# Modemplatine_modem_1_1.net
KiCad netlist of a schematic drawn in EAGLE
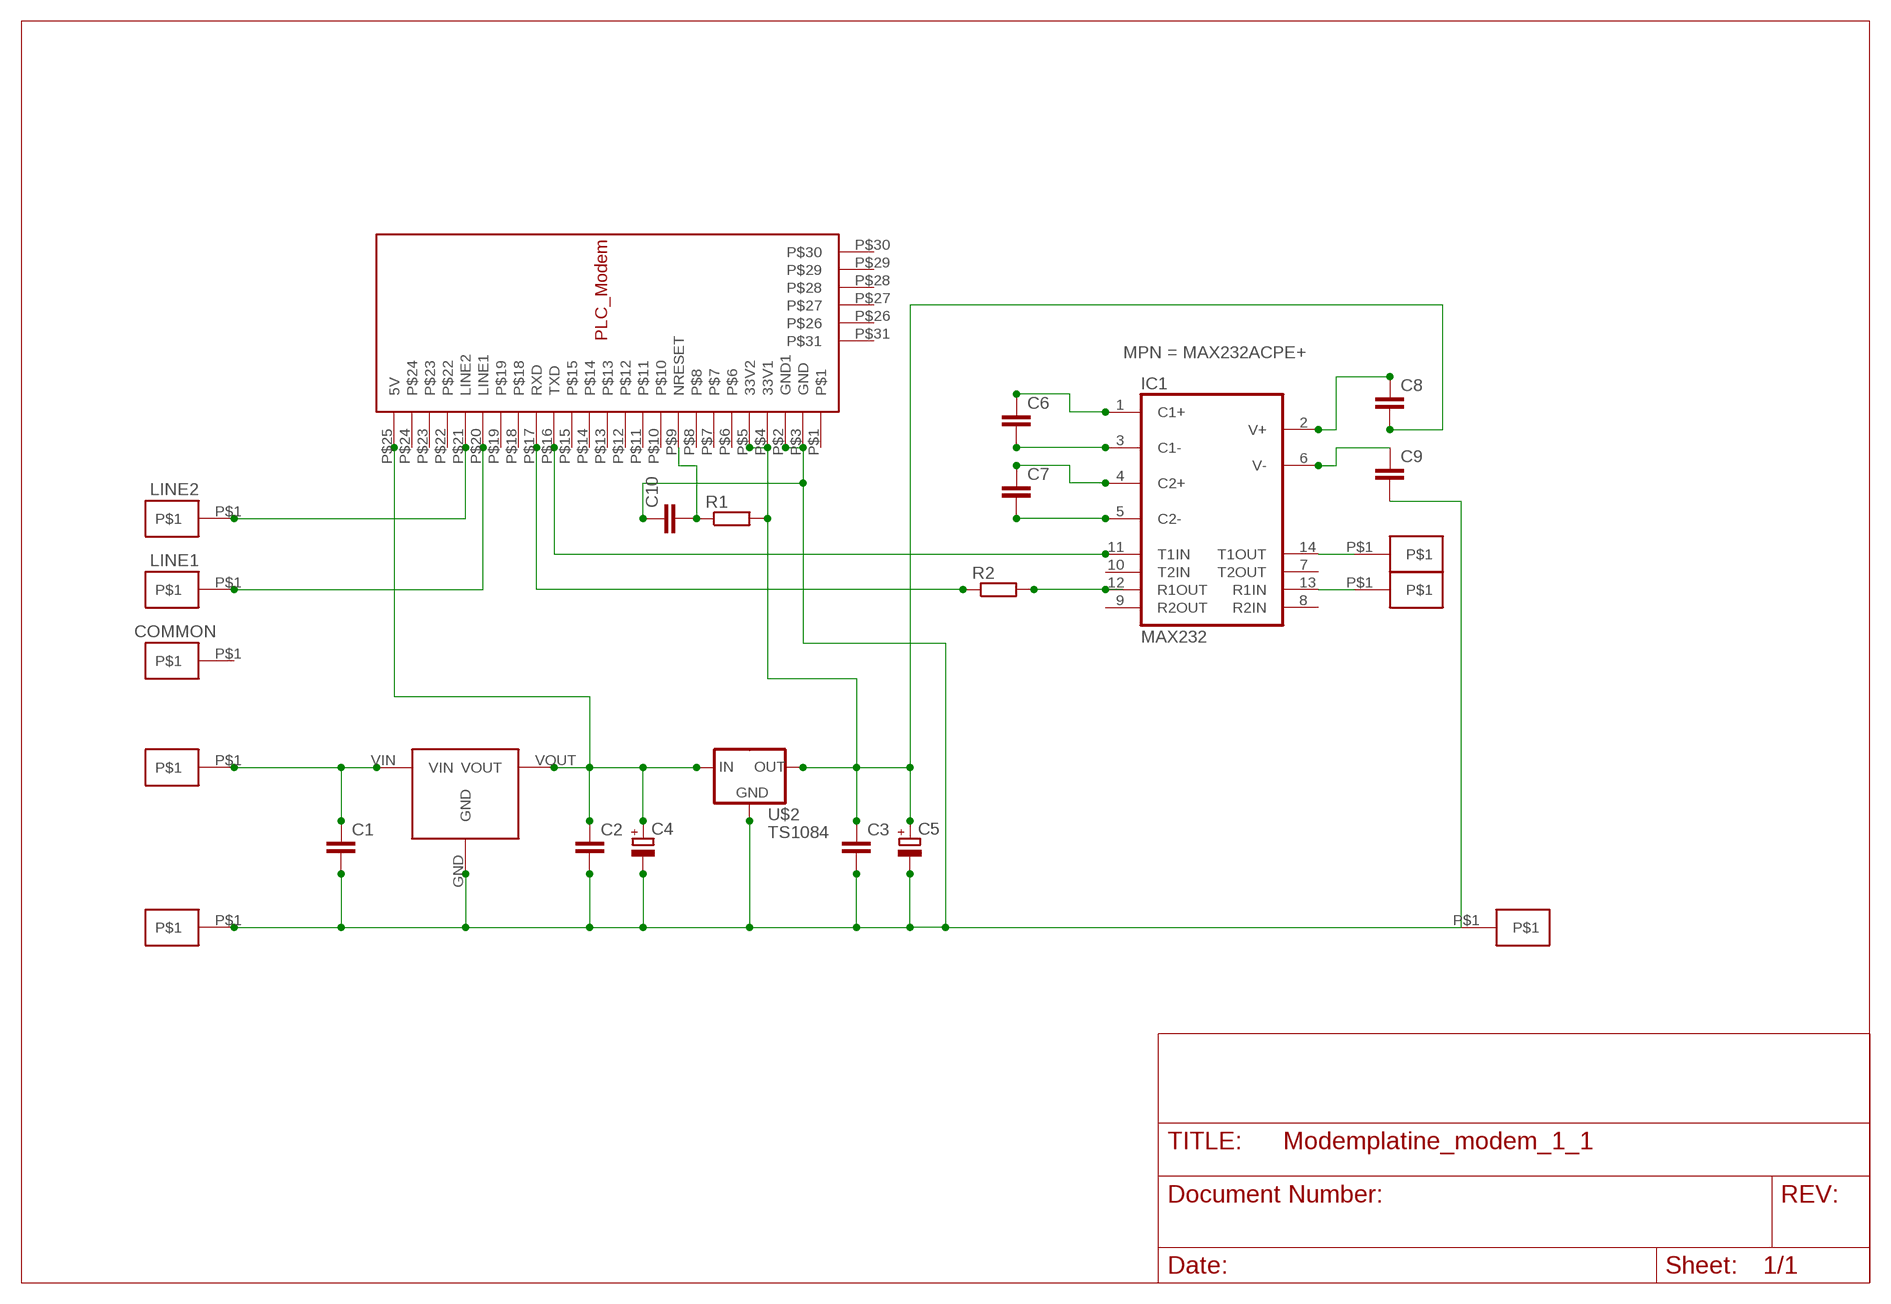
[diagram p0: schematic, sheet 1]

(export (version "E")
  (design (tool "Eeschema 10.0.6"))
  (components
    (comp (ref "C1")
      (value "C2.5/5")
      (footprint "eagle-import:C2.5-5")
      (libsource (lib "eagle-import") (part "C2.5/5"))
    )
    (comp (ref "C2")
      (value "C2.5/5")
      (footprint "eagle-import:C2.5-5")
      (libsource (lib "eagle-import") (part "C2.5/5"))
    )
    (comp (ref "C3")
      (value "C2.5/5")
      (footprint "eagle-import:C2.5-5")
      (libsource (lib "eagle-import") (part "C2.5/5"))
    )
    (comp (ref "C4")
      (value "CPOL-EUE2.5-5")
      (footprint "eagle-import:E2,5-5")
      (libsource (lib "eagle-import") (part "CPOL-EUE2.5-5"))
    )
    (comp (ref "C5")
      (value "CPOL-EUE2.5-5")
      (footprint "eagle-import:E2,5-5")
      (libsource (lib "eagle-import") (part "CPOL-EUE2.5-5"))
    )
    (comp (ref "C6")
      (value "C-EU025-040X050")
      (footprint "eagle-import:C025-040X050")
      (libsource (lib "eagle-import") (part "C-EU025-040X050"))
    )
    (comp (ref "C7")
      (value "C-EU025-040X050")
      (footprint "eagle-import:C025-040X050")
      (libsource (lib "eagle-import") (part "C-EU025-040X050"))
    )
    (comp (ref "C8")
      (value "C-EU025-040X050")
      (footprint "eagle-import:C025-040X050")
      (libsource (lib "eagle-import") (part "C-EU025-040X050"))
    )
    (comp (ref "C9")
      (value "C-EU025-040X050")
      (footprint "eagle-import:C025-040X050")
      (libsource (lib "eagle-import") (part "C-EU025-040X050"))
    )
    (comp (ref "C10")
      (value "C-EU025-040X050")
      (footprint "eagle-import:C025-040X050")
      (libsource (lib "eagle-import") (part "C-EU025-040X050"))
    )
    (comp (ref "IC1")
      (value "MAX232")
      (footprint "eagle-import:DIL16")
      (fields
        (field (name "MF") "MAXIM")
        (field (name "MPN") "MAX232ACPE+")
        (field (name "MPN_1") "MAX232ACPE+")
      )
      (libsource (lib "eagle-import") (part "MAX232"))
    )
    (comp (ref "LINE1")
      (value "PN4")
      (footprint "eagle-import:PIN2")
      (libsource (lib "eagle-import") (part "PN4"))
    )
    (comp (ref "LINE2")
      (value "PN4")
      (footprint "eagle-import:PIN2")
      (libsource (lib "eagle-import") (part "PN4"))
    )
    (comp (ref "R1")
      (value "R-EU_0207/10")
      (footprint "eagle-import:0207_10")
      (libsource (lib "eagle-import") (part "R-EU_0207/10"))
    )
    (comp (ref "R2")
      (value "R-EU_0207/10")
      (footprint "eagle-import:0207_10")
      (libsource (lib "eagle-import") (part "R-EU_0207/10"))
    )
    (comp (ref "U$1")
      (value "RECOM_785_05")
      (footprint "eagle-import:RECOM785X")
      (libsource (lib "eagle-import") (part "RECOM_785_05"))
    )
    (comp (ref "U$2")
      (value "TS1084")
      (footprint "eagle-import:TS1084")
      (libsource (lib "eagle-import") (part "TS1084"))
    )
    (comp (ref "U$3")
      (value "MODEMSTECKER")
      (footprint "eagle-import:MODEM_FUSS")
      (libsource (lib "eagle-import") (part "MODEMSTECKER"))
    )
    (comp (ref "U$4")
      (value "PN4")
      (footprint "eagle-import:PIN2")
      (libsource (lib "eagle-import") (part "PN4"))
    )
    (comp (ref "U$5")
      (value "PN4")
      (footprint "eagle-import:PIN2")
      (libsource (lib "eagle-import") (part "PN4"))
    )
    (comp (ref "U$6")
      (value "PN4")
      (footprint "eagle-import:PIN2")
      (libsource (lib "eagle-import") (part "PN4"))
    )
    (comp (ref "U$7")
      (value "PN4")
      (footprint "eagle-import:PIN2")
      (libsource (lib "eagle-import") (part "PN4"))
    )
    (comp (ref "U$8")
      (value "PN4")
      (footprint "eagle-import:PIN2")
      (libsource (lib "eagle-import") (part "PN4"))
    )
    (comp (ref "U$11")
      (value "PN4")
      (footprint "eagle-import:PIN2")
      (libsource (lib "eagle-import") (part "PN4"))
    )
  )
  (nets
    (net (code "1") (name "Net-(C1-Pad1)") (class "Default")
      (node (ref "C1") (pin "1") (pinfunction "1_1") (pintype "passive"))
      (node (ref "U$1") (pin "VIN") (pinfunction "VIN_VIN") (pintype "bidirectional"))
      (node (ref "U$5") (pin "P$1") (pinfunction "P$1_P$1") (pintype "bidirectional"))
    )
    (net (code "2") (name "Net-(IC1A-C1+)") (class "Default")
      (node (ref "C6") (pin "1") (pinfunction "1_1") (pintype "passive"))
      (node (ref "IC1") (pin "1") (pinfunction "C1+_1") (pintype "bidirectional"))
    )
    (net (code "3") (name "Net-(IC1A-C1-)") (class "Default")
      (node (ref "C6") (pin "2") (pinfunction "2_2") (pintype "passive"))
      (node (ref "IC1") (pin "3") (pinfunction "C1-_3") (pintype "bidirectional"))
    )
    (net (code "4") (name "Net-(IC1A-C2+)") (class "Default")
      (node (ref "C7") (pin "1") (pinfunction "1_1") (pintype "passive"))
      (node (ref "IC1") (pin "4") (pinfunction "C2+_4") (pintype "bidirectional"))
    )
    (net (code "5") (name "Net-(IC1A-C2-)") (class "Default")
      (node (ref "C7") (pin "2") (pinfunction "2_2") (pintype "passive"))
      (node (ref "IC1") (pin "5") (pinfunction "C2-_5") (pintype "bidirectional"))
    )
    (net (code "6") (name "Net-(IC1A-R1IN)") (class "Default")
      (node (ref "IC1") (pin "13") (pinfunction "R1IN_13") (pintype "input"))
      (node (ref "U$7") (pin "P$1") (pinfunction "P$1_P$1") (pintype "bidirectional"))
    )
    (net (code "7") (name "Net-(IC1A-R1OUT)") (class "Default")
      (node (ref "IC1") (pin "12") (pinfunction "R1OUT_12") (pintype "output"))
      (node (ref "R2") (pin "2") (pinfunction "2_2") (pintype "passive"))
    )
    (net (code "8") (name "Net-(IC1A-T1IN)") (class "Default")
      (node (ref "IC1") (pin "11") (pinfunction "T1IN_11") (pintype "input"))
      (node (ref "U$3") (pin "P$16") (pinfunction "TXD_P$16") (pintype "bidirectional"))
    )
    (net (code "9") (name "Net-(IC1A-T1OUT)") (class "Default")
      (node (ref "IC1") (pin "14") (pinfunction "T1OUT_14") (pintype "output"))
      (node (ref "U$6") (pin "P$1") (pinfunction "P$1_P$1") (pintype "bidirectional"))
    )
    (net (code "10") (name "Net-(IC1A-V+)") (class "Default")
      (node (ref "C8") (pin "1") (pinfunction "1_1") (pintype "passive"))
      (node (ref "IC1") (pin "2") (pinfunction "V+_2") (pintype "bidirectional"))
    )
    (net (code "11") (name "Net-(IC1A-V-)") (class "Default")
      (node (ref "C9") (pin "1") (pinfunction "1_1") (pintype "passive"))
      (node (ref "IC1") (pin "6") (pinfunction "V-_6") (pintype "bidirectional"))
    )
    (net (code "12") (name "Net-(U$2-GND)") (class "Default")
      (node (ref "C1") (pin "2") (pinfunction "2_2") (pintype "passive"))
      (node (ref "C10") (pin "1") (pinfunction "1_1") (pintype "passive"))
      (node (ref "C2") (pin "2") (pinfunction "2_2") (pintype "passive"))
      (node (ref "C3") (pin "2") (pinfunction "2_2") (pintype "passive"))
      (node (ref "C4") (pin "-") (pinfunction "-_-") (pintype "passive"))
      (node (ref "C5") (pin "-") (pinfunction "-_-") (pintype "passive"))
      (node (ref "C9") (pin "2") (pinfunction "2_2") (pintype "passive"))
      (node (ref "U$1") (pin "GND") (pinfunction "GND_GND") (pintype "bidirectional"))
      (node (ref "U$2") (pin "1GND") (pinfunction "GND_1GND") (pintype "input"))
      (node (ref "U$3") (pin "P$2") (pinfunction "GND1_P$2") (pintype "bidirectional"))
      (node (ref "U$3") (pin "P$3") (pinfunction "GND_P$3") (pintype "bidirectional"))
      (node (ref "U$4") (pin "P$1") (pinfunction "P$1_P$1") (pintype "bidirectional"))
      (node (ref "U$8") (pin "P$1") (pinfunction "P$1_P$1") (pintype "bidirectional"))
    )
    (net (code "13") (name "Net-(U$2-IN)") (class "Default")
      (node (ref "C2") (pin "1") (pinfunction "1_1") (pintype "passive"))
      (node (ref "C4") (pin "+") (pinfunction "+_+") (pintype "passive"))
      (node (ref "U$1") (pin "VOUT") (pinfunction "VOUT_VOUT") (pintype "bidirectional"))
      (node (ref "U$2") (pin "3IN") (pinfunction "IN_3IN") (pintype "input"))
      (node (ref "U$3") (pin "P$25") (pinfunction "5V_P$25") (pintype "bidirectional"))
    )
    (net (code "14") (name "Net-(U$2-OUT)") (class "Default")
      (node (ref "C3") (pin "1") (pinfunction "1_1") (pintype "passive"))
      (node (ref "C5") (pin "+") (pinfunction "+_+") (pintype "passive"))
      (node (ref "C8") (pin "2") (pinfunction "2_2") (pintype "passive"))
      (node (ref "R1") (pin "2") (pinfunction "2_2") (pintype "passive"))
      (node (ref "U$2") (pin "2OUT") (pinfunction "OUT_2OUT") (pintype "passive"))
      (node (ref "U$3") (pin "P$4") (pinfunction "33V1_P$4") (pintype "bidirectional"))
      (node (ref "U$3") (pin "P$5") (pinfunction "33V2_P$5") (pintype "bidirectional"))
    )
    (net (code "15") (name "Net-(U$3-LINE1)") (class "Default")
      (node (ref "LINE1") (pin "P$1") (pinfunction "P$1_P$1") (pintype "bidirectional"))
      (node (ref "U$3") (pin "P$20") (pinfunction "LINE1_P$20") (pintype "bidirectional"))
    )
    (net (code "16") (name "Net-(U$3-LINE2)") (class "Default")
      (node (ref "LINE2") (pin "P$1") (pinfunction "P$1_P$1") (pintype "bidirectional"))
      (node (ref "U$3") (pin "P$21") (pinfunction "LINE2_P$21") (pintype "bidirectional"))
    )
    (net (code "17") (name "Net-(U$3-NRESET)") (class "Default")
      (node (ref "C10") (pin "2") (pinfunction "2_2") (pintype "passive"))
      (node (ref "R1") (pin "1") (pinfunction "1_1") (pintype "passive"))
      (node (ref "U$3") (pin "P$9") (pinfunction "NRESET_P$9") (pintype "bidirectional"))
    )
    (net (code "18") (name "Net-(U$3-RXD)") (class "Default")
      (node (ref "R2") (pin "1") (pinfunction "1_1") (pintype "passive"))
      (node (ref "U$3") (pin "P$17") (pinfunction "RXD_P$17") (pintype "bidirectional"))
    )
    (net (code "19") (name "unconnected-(IC1A-R2IN-Pad8)") (class "Default")
      (node (ref "IC1") (pin "8") (pinfunction "R2IN_8") (pintype "input"))
    )
    (net (code "20") (name "unconnected-(IC1A-R2OUT-Pad9)") (class "Default")
      (node (ref "IC1") (pin "9") (pinfunction "R2OUT_9") (pintype "output"))
    )
    (net (code "21") (name "unconnected-(IC1A-T2IN-Pad10)") (class "Default")
      (node (ref "IC1") (pin "10") (pinfunction "T2IN_10") (pintype "input"))
    )
    (net (code "22") (name "unconnected-(IC1A-T2OUT-Pad7)") (class "Default")
      (node (ref "IC1") (pin "7") (pinfunction "T2OUT_7") (pintype "output"))
    )
    (net (code "23") (name "unconnected-(U$3-PadP$1)") (class "Default")
      (node (ref "U$3") (pin "P$1") (pinfunction "P$1_P$1") (pintype "bidirectional"))
    )
    (net (code "24") (name "unconnected-(U$3-PadP$6)") (class "Default")
      (node (ref "U$3") (pin "P$6") (pinfunction "P$6_P$6") (pintype "bidirectional"))
    )
    (net (code "25") (name "unconnected-(U$3-PadP$7)") (class "Default")
      (node (ref "U$3") (pin "P$7") (pinfunction "P$7_P$7") (pintype "bidirectional"))
    )
    (net (code "26") (name "unconnected-(U$3-PadP$8)") (class "Default")
      (node (ref "U$3") (pin "P$8") (pinfunction "P$8_P$8") (pintype "bidirectional"))
    )
    (net (code "27") (name "unconnected-(U$3-PadP$10)") (class "Default")
      (node (ref "U$3") (pin "P$10") (pinfunction "P$10_P$10") (pintype "bidirectional"))
    )
    (net (code "28") (name "unconnected-(U$3-PadP$11)") (class "Default")
      (node (ref "U$3") (pin "P$11") (pinfunction "P$11_P$11") (pintype "bidirectional"))
    )
    (net (code "29") (name "unconnected-(U$3-PadP$12)") (class "Default")
      (node (ref "U$3") (pin "P$12") (pinfunction "P$12_P$12") (pintype "bidirectional"))
    )
    (net (code "30") (name "unconnected-(U$3-PadP$13)") (class "Default")
      (node (ref "U$3") (pin "P$13") (pinfunction "P$13_P$13") (pintype "bidirectional"))
    )
    (net (code "31") (name "unconnected-(U$3-PadP$14)") (class "Default")
      (node (ref "U$3") (pin "P$14") (pinfunction "P$14_P$14") (pintype "bidirectional"))
    )
    (net (code "32") (name "unconnected-(U$3-PadP$15)") (class "Default")
      (node (ref "U$3") (pin "P$15") (pinfunction "P$15_P$15") (pintype "bidirectional"))
    )
    (net (code "33") (name "unconnected-(U$3-PadP$18)") (class "Default")
      (node (ref "U$3") (pin "P$18") (pinfunction "P$18_P$18") (pintype "bidirectional"))
    )
    (net (code "34") (name "unconnected-(U$3-PadP$19)") (class "Default")
      (node (ref "U$3") (pin "P$19") (pinfunction "P$19_P$19") (pintype "bidirectional"))
    )
    (net (code "35") (name "unconnected-(U$3-PadP$22)") (class "Default")
      (node (ref "U$3") (pin "P$22") (pinfunction "P$22_P$22") (pintype "bidirectional"))
    )
    (net (code "36") (name "unconnected-(U$3-PadP$23)") (class "Default")
      (node (ref "U$3") (pin "P$23") (pinfunction "P$23_P$23") (pintype "bidirectional"))
    )
    (net (code "37") (name "unconnected-(U$3-PadP$24)") (class "Default")
      (node (ref "U$3") (pin "P$24") (pinfunction "P$24_P$24") (pintype "bidirectional"))
    )
    (net (code "38") (name "unconnected-(U$3-PadP$26)") (class "Default")
      (node (ref "U$3") (pin "P$26") (pinfunction "P$26_P$26") (pintype "bidirectional"))
    )
    (net (code "39") (name "unconnected-(U$3-PadP$27)") (class "Default")
      (node (ref "U$3") (pin "P$27") (pinfunction "P$27_P$27") (pintype "bidirectional"))
    )
    (net (code "40") (name "unconnected-(U$3-PadP$28)") (class "Default")
      (node (ref "U$3") (pin "P$28") (pinfunction "P$28_P$28") (pintype "bidirectional"))
    )
    (net (code "41") (name "unconnected-(U$3-PadP$29)") (class "Default")
      (node (ref "U$3") (pin "P$29") (pinfunction "P$29_P$29") (pintype "bidirectional"))
    )
    (net (code "42") (name "unconnected-(U$3-PadP$30)") (class "Default")
      (node (ref "U$3") (pin "P$30") (pinfunction "P$30_P$30") (pintype "bidirectional"))
    )
    (net (code "43") (name "unconnected-(U$3-PadP$31)") (class "Default")
      (node (ref "U$3") (pin "P$31") (pinfunction "P$31_P$31") (pintype "bidirectional"))
    )
    (net (code "44") (name "unconnected-(U$11-PadP$1)") (class "Default")
      (node (ref "U$11") (pin "P$1") (pinfunction "P$1_P$1") (pintype "bidirectional"))
    )
  )
)
